# hackathon_trophy.net
KiCad netlist of a schematic drawn in EAGLE
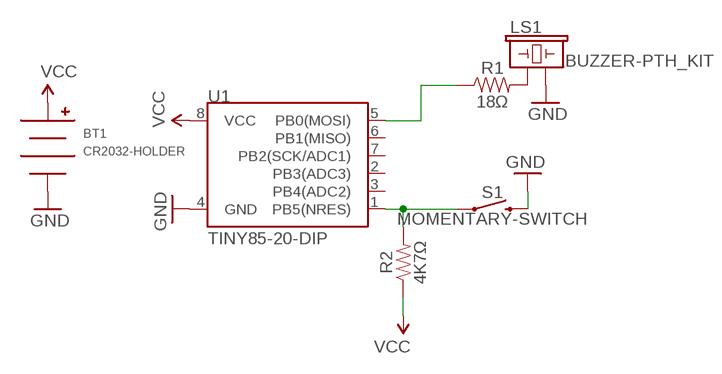
[diagram p0: schematic, sheet 1]

(export (version "E")
  (design (tool "Eeschema 10.0.6"))
  (components
    (comp (ref "BT1")
      (value "CR2032-HOLDER")
      (footprint "eagle-import:CH28-2032LF")
      (libsource (lib "eagle-import") (part "CR2032-HOLDER"))
    )
    (comp (ref "LS1")
      (value "BUZZER-PTH_KIT")
      (footprint "eagle-import:BUZZER-12MM-KIT")
      (libsource (lib "eagle-import") (part "BUZZER-PTH_KIT"))
    )
    (comp (ref "R1")
      (value "18Ω")
      (footprint "eagle-import:1206")
      (libsource (lib "eagle-import") (part "RESISTOR1206"))
    )
    (comp (ref "R2")
      (value "4K7Ω")
      (footprint "eagle-import:1206")
      (libsource (lib "eagle-import") (part "RESISTOR1206"))
    )
    (comp (ref "S1")
      (value "MOMENTARY-SWITCH")
      (footprint "eagle-import:TACTILE_SWITCH_PTH_6.0MM_KIT")
      (libsource (lib "eagle-import") (part "MOMENTARY-SWITCH-SPST-PTH-6.0MM-KIT"))
    )
    (comp (ref "U1")
      (value "TINY85-20-DIP")
      (footprint "eagle-import:DIP08_MCU")
      (libsource (lib "eagle-import") (part "ATTINY45TINY85-20-DIP"))
    )
  )
  (nets
    (net (code "1") (name "GND") (class "Default")
      (node (ref "BT1") (pin "NEG") (pinfunction "NEG_NEG") (pintype "bidirectional"))
      (node (ref "LS1") (pin "-") (pinfunction "2_-") (pintype "passive"))
      (node (ref "S1") (pin "3") (pinfunction "2_3") (pintype "passive"))
      (node (ref "U1") (pin "4") (pinfunction "GND_4") (pintype "bidirectional"))
    )
    (net (code "2") (name "Net-(LS1-1)") (class "Default")
      (node (ref "LS1") (pin "+") (pinfunction "1_+") (pintype "passive"))
      (node (ref "R1") (pin "2") (pinfunction "2_2") (pintype "passive"))
    )
    (net (code "3") (name "Net-(U1-PB0(MOSI))") (class "Default")
      (node (ref "R1") (pin "1") (pinfunction "1_1") (pintype "passive"))
      (node (ref "U1") (pin "5") (pinfunction "PB0(MOSI)_5") (pintype "bidirectional"))
    )
    (net (code "4") (name "Net-(U1-PB5(NRES))") (class "Default")
      (node (ref "R2") (pin "2") (pinfunction "2_2") (pintype "passive"))
      (node (ref "S1") (pin "1") (pinfunction "1_1") (pintype "passive"))
      (node (ref "U1") (pin "1") (pinfunction "PB5(NRES)_1") (pintype "bidirectional"))
    )
    (net (code "5") (name "VCC") (class "Default")
      (node (ref "BT1") (pin "POS") (pinfunction "POS_POS") (pintype "bidirectional"))
      (node (ref "R2") (pin "1") (pinfunction "1_1") (pintype "passive"))
      (node (ref "U1") (pin "8") (pinfunction "VCC_8") (pintype "bidirectional"))
    )
    (net (code "6") (name "unconnected-(U1-PB1(MISO)-Pad6)") (class "Default")
      (node (ref "U1") (pin "6") (pinfunction "PB1(MISO)_6") (pintype "bidirectional"))
    )
    (net (code "7") (name "unconnected-(U1-PB2(SCK{slash}ADC1)-Pad7)") (class "Default")
      (node (ref "U1") (pin "7") (pinfunction "PB2(SCK/ADC1)_7") (pintype "bidirectional"))
    )
    (net (code "8") (name "unconnected-(U1-PB3(ADC3)-Pad2)") (class "Default")
      (node (ref "U1") (pin "2") (pinfunction "PB3(ADC3)_2") (pintype "bidirectional"))
    )
    (net (code "9") (name "unconnected-(U1-PB4(ADC2)-Pad3)") (class "Default")
      (node (ref "U1") (pin "3") (pinfunction "PB4(ADC2)_3") (pintype "bidirectional"))
    )
  )
)
